# jtag.net
KiCad netlist of a schematic drawn in Altium Designer
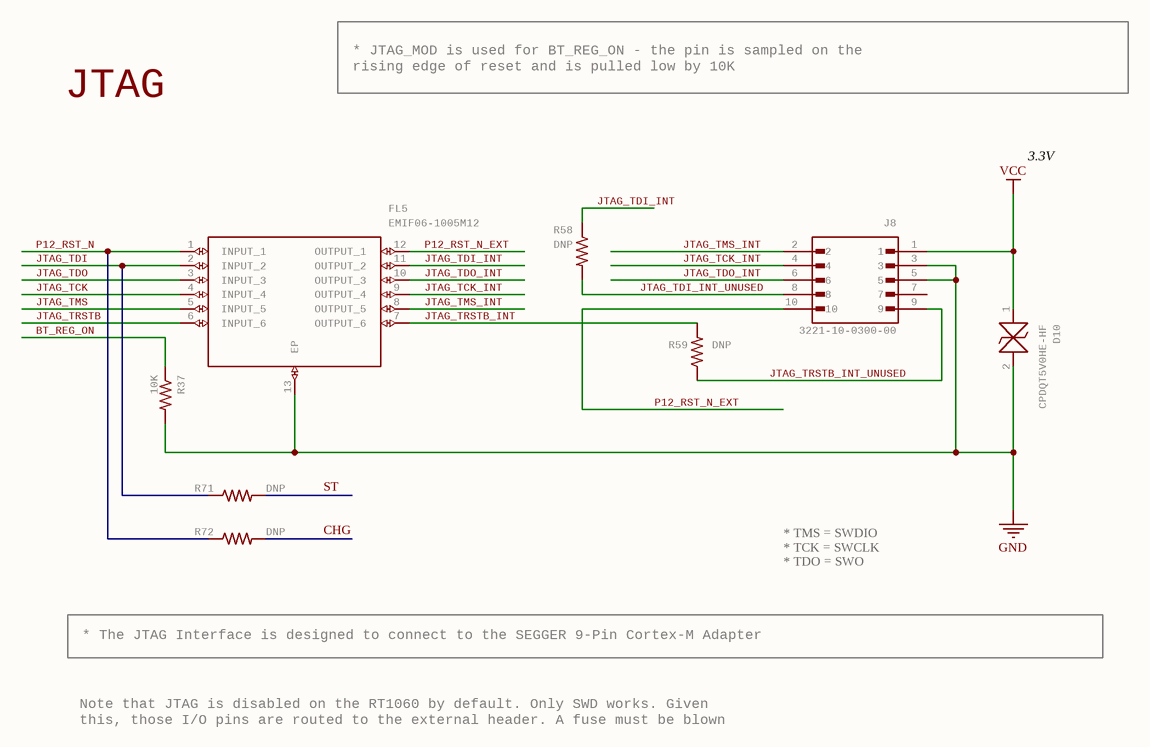
[diagram p0: jtag.SchDoc]

(export (version "E")
  (design (tool "Eeschema 10.0.6"))
  (components
    (comp (ref "D10")
      (value "CPDQT5V0HE-HF")
      (footprint "CPDQT5V0HEHF")
      (description "ESD Suppressors / TVS Diodes DIODE ESD 5VWM 65W 0402/SOD-923F   Source:  Datasheet")
      (fields (field (name "MOUSER_PART_NUMBER") "MOUSER_PART_NUMBER"))
      (libsource (lib "rt10") (part "CPDQT5V0HE-HF"))
    )
    (comp (ref "FL5")
      (value "EMIF06-1005M12")
      (footprint "SON40P150X250X65-13N")
      (description "EMI Filter Circuits 6lin lw cpcitnc EMI 45pF -35db @ 900MHz   Source:  Datasheet")
      (fields (field (name "MOUSER_PART_NUMBER") "511-EMIF06-1005M12"))
      (libsource (lib "rt10") (part "EMIF06-1005M12"))
    )
    (comp (ref "J8")
      (value "3221-10-0300-00")
      (footprint "CNC_3221-10-0300-00")
      (description "Check availability")
      (fields (field (name "MF") "CNC Tech"))
      (libsource (lib "rt10") (part "3221-10-0300-00"))
    )
    (comp (ref "R37")
      (value "10K")
      (footprint "0402-RES")
      (description "ResistorBasic schematic elements and footprints for 0603, 1206, and PTH resistors.")
      (fields (field (name "MPN") "AC0402FR-1310KL"))
      (libsource (lib "rt10") (part "RESISTOR0402-RES"))
    )
    (comp (ref "R58")
      (value "DNP")
      (footprint "0402-RES")
      (description "ResistorBasic schematic elements and footprints for 0603, 1206, and PTH resistors.")
      (libsource (lib "rt10") (part "RESISTOR0402-RES"))
    )
    (comp (ref "R59")
      (value "DNP")
      (footprint "0402-RES")
      (description "ResistorBasic schematic elements and footprints for 0603, 1206, and PTH resistors.")
      (libsource (lib "rt10") (part "RESISTOR0402-RES"))
    )
    (comp (ref "R71")
      (value "DNP")
      (footprint "0402-RES")
      (description "ResistorBasic schematic elements and footprints for 0603, 1206, and PTH resistors.")
      (libsource (lib "rt10") (part "RESISTOR0402-RES"))
    )
    (comp (ref "R72")
      (value "DNP")
      (footprint "0402-RES")
      (description "ResistorBasic schematic elements and footprints for 0603, 1206, and PTH resistors.")
      (libsource (lib "rt10") (part "RESISTOR0402-RES"))
    )
  )
  (nets
    (net (code "1") (name "/BT_REG_ON") (class "Default")
      (node (ref "R37") (pin "1") (pinfunction "1_1") (pintype "passive"))
    )
    (net (code "2") (name "/CHG") (class "Default")
      (node (ref "R72") (pin "2") (pinfunction "2_2") (pintype "passive"))
    )
    (net (code "3") (name "/JTAG_TCK") (class "Default")
      (node (ref "FL5") (pin "4") (pinfunction "INPUT_4_4") (pintype "bidirectional"))
    )
    (net (code "4") (name "/JTAG_TCK_INT") (class "Default")
      (node (ref "FL5") (pin "9") (pinfunction "OUTPUT_4_9") (pintype "bidirectional"))
      (node (ref "J8") (pin "4") (pinfunction "4_4") (pintype "passive"))
    )
    (net (code "5") (name "/JTAG_TDI") (class "Default")
      (node (ref "FL5") (pin "2") (pinfunction "INPUT_2_2") (pintype "bidirectional"))
      (node (ref "R71") (pin "1") (pinfunction "1_1") (pintype "passive"))
    )
    (net (code "6") (name "/JTAG_TDI_INT") (class "Default")
      (node (ref "FL5") (pin "11") (pinfunction "OUTPUT_2_11") (pintype "bidirectional"))
      (node (ref "R58") (pin "1") (pinfunction "1_1") (pintype "passive"))
    )
    (net (code "7") (name "/JTAG_TDI_INT_UNUSED") (class "Default")
      (node (ref "J8") (pin "8") (pinfunction "8_8") (pintype "passive"))
      (node (ref "R58") (pin "2") (pinfunction "2_2") (pintype "passive"))
    )
    (net (code "8") (name "/JTAG_TDO") (class "Default")
      (node (ref "FL5") (pin "3") (pinfunction "INPUT_3_3") (pintype "bidirectional"))
    )
    (net (code "9") (name "/JTAG_TDO_INT") (class "Default")
      (node (ref "FL5") (pin "10") (pinfunction "OUTPUT_3_10") (pintype "bidirectional"))
      (node (ref "J8") (pin "6") (pinfunction "6_6") (pintype "passive"))
    )
    (net (code "10") (name "/JTAG_TMS") (class "Default")
      (node (ref "FL5") (pin "5") (pinfunction "INPUT_5_5") (pintype "bidirectional"))
    )
    (net (code "11") (name "/JTAG_TMS_INT") (class "Default")
      (node (ref "FL5") (pin "8") (pinfunction "OUTPUT_5_8") (pintype "bidirectional"))
      (node (ref "J8") (pin "2") (pinfunction "2_2") (pintype "passive"))
    )
    (net (code "12") (name "/JTAG_TRSTB") (class "Default")
      (node (ref "FL5") (pin "6") (pinfunction "INPUT_6_6") (pintype "bidirectional"))
    )
    (net (code "13") (name "/JTAG_TRSTB_INT") (class "Default")
      (node (ref "FL5") (pin "7") (pinfunction "OUTPUT_6_7") (pintype "bidirectional"))
      (node (ref "R59") (pin "2") (pinfunction "2_2") (pintype "passive"))
    )
    (net (code "14") (name "/JTAG_TRSTB_INT_UNUSED") (class "Default")
      (node (ref "J8") (pin "9") (pinfunction "9_9") (pintype "passive"))
      (node (ref "R59") (pin "1") (pinfunction "1_1") (pintype "passive"))
    )
    (net (code "15") (name "/P12_RST_N") (class "Default")
      (node (ref "FL5") (pin "1") (pinfunction "INPUT_1_1") (pintype "bidirectional"))
      (node (ref "R72") (pin "1") (pinfunction "1_1") (pintype "passive"))
    )
    (net (code "16") (name "/P12_RST_N_EXT") (class "Default")
      (node (ref "FL5") (pin "12") (pinfunction "OUTPUT_1_12") (pintype "bidirectional"))
      (node (ref "J8") (pin "10") (pinfunction "10_10") (pintype "passive"))
    )
    (net (code "17") (name "/ST") (class "Default")
      (node (ref "R71") (pin "2") (pinfunction "2_2") (pintype "passive"))
    )
    (net (code "18") (name "GND") (class "Default")
      (node (ref "D10") (pin "2") (pinfunction "2_2") (pintype "bidirectional"))
      (node (ref "FL5") (pin "13") (pinfunction "EP_13") (pintype "bidirectional"))
      (node (ref "J8") (pin "3") (pinfunction "3_3") (pintype "passive"))
      (node (ref "J8") (pin "5") (pinfunction "5_5") (pintype "passive"))
      (node (ref "R37") (pin "2") (pinfunction "2_2") (pintype "passive"))
    )
    (net (code "19") (name "VCC") (class "Default")
      (node (ref "D10") (pin "1") (pinfunction "1_1") (pintype "bidirectional"))
      (node (ref "J8") (pin "1") (pinfunction "1_1") (pintype "passive"))
    )
    (net (code "20") (name "unconnected-(J8-Pad7)") (class "Default")
      (node (ref "J8") (pin "7") (pinfunction "7_7") (pintype "passive"))
    )
  )
)
